# SCH.net
KiCad netlist of a schematic drawn in Altium Designer
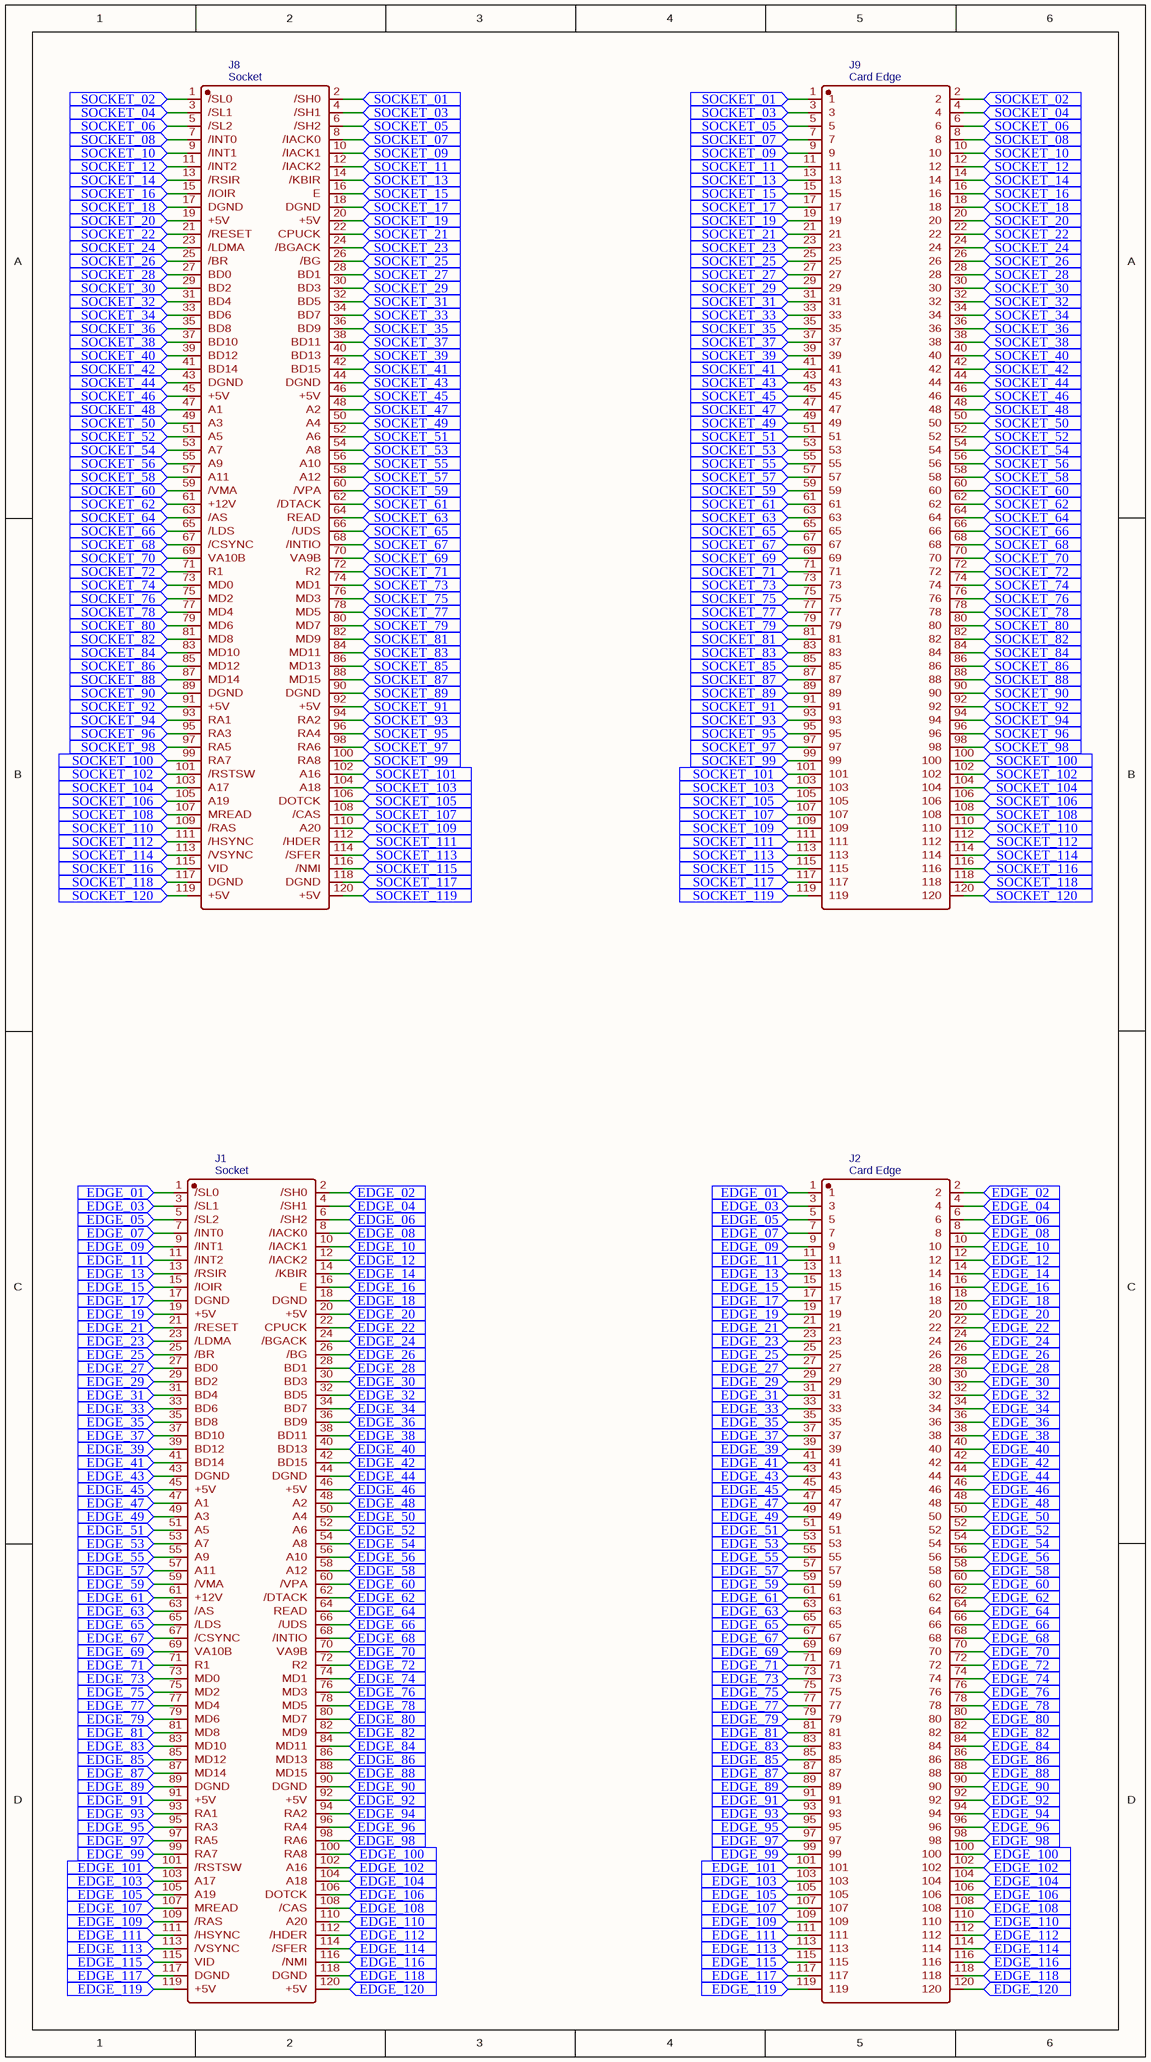
[diagram p0: SCH.schdoc]

(export (version "E")
  (design (tool "Eeschema 10.0.6"))
  (components
    (comp (ref "J1")
      (value "Socket")
      (fields
        (field (name "BOM_MANUFACTURER PART") "345-120-520-201")
        (field (name "BOM_SUPPLIER PART") "587-345-120-520-201")
        (field (name "CONTRIBUTOR") "AlexTheCat123")
      )
      (libsource (lib "altium-import") (part "root_0_Socket_"))
    )
    (comp (ref "J2")
      (value "Card Edge")
      (fields
        (field (name "BOM_MANUFACTURER PART") "345-120-520-201")
        (field (name "BOM_SUPPLIER PART") "587-345-120-520-201")
        (field (name "CONTRIBUTOR") "AlexTheCat123")
      )
      (libsource (lib "altium-import") (part "root_0_Card Edge_"))
    )
    (comp (ref "J8")
      (value "Socket")
      (fields
        (field (name "BOM_MANUFACTURER PART") "345-120-520-201")
        (field (name "BOM_SUPPLIER PART") "587-345-120-520-201")
        (field (name "CONTRIBUTOR") "AlexTheCat123")
      )
      (libsource (lib "altium-import") (part "root_0_Socket_"))
    )
    (comp (ref "J9")
      (value "Card Edge")
      (fields
        (field (name "BOM_MANUFACTURER PART") "345-120-520-201")
        (field (name "BOM_SUPPLIER PART") "587-345-120-520-201")
        (field (name "CONTRIBUTOR") "AlexTheCat123")
      )
      (libsource (lib "altium-import") (part "root_0_Card Edge_"))
    )
  )
  (nets
    (net (code "1") (name "/EDGE_01") (class "Default")
      (node (ref "J1") (pin "1") (pinfunction "/SL0_1") (pintype "passive"))
      (node (ref "J2") (pin "1") (pinfunction "1_1") (pintype "passive"))
    )
    (net (code "2") (name "/EDGE_02") (class "Default")
      (node (ref "J1") (pin "2") (pinfunction "/SH0_2") (pintype "passive"))
      (node (ref "J2") (pin "2") (pinfunction "2_2") (pintype "passive"))
    )
    (net (code "3") (name "/EDGE_03") (class "Default")
      (node (ref "J1") (pin "3") (pinfunction "/SL1_3") (pintype "passive"))
      (node (ref "J2") (pin "3") (pinfunction "3_3") (pintype "passive"))
    )
    (net (code "4") (name "/EDGE_04") (class "Default")
      (node (ref "J1") (pin "4") (pinfunction "/SH1_4") (pintype "passive"))
      (node (ref "J2") (pin "4") (pinfunction "4_4") (pintype "passive"))
    )
    (net (code "5") (name "/EDGE_05") (class "Default")
      (node (ref "J1") (pin "5") (pinfunction "/SL2_5") (pintype "passive"))
      (node (ref "J2") (pin "5") (pinfunction "5_5") (pintype "passive"))
    )
    (net (code "6") (name "/EDGE_06") (class "Default")
      (node (ref "J1") (pin "6") (pinfunction "/SH2_6") (pintype "passive"))
      (node (ref "J2") (pin "6") (pinfunction "6_6") (pintype "passive"))
    )
    (net (code "7") (name "/EDGE_07") (class "Default")
      (node (ref "J1") (pin "7") (pinfunction "/INT0_7") (pintype "passive"))
      (node (ref "J2") (pin "7") (pinfunction "7_7") (pintype "passive"))
    )
    (net (code "8") (name "/EDGE_08") (class "Default")
      (node (ref "J1") (pin "8") (pinfunction "/IACK0_8") (pintype "passive"))
      (node (ref "J2") (pin "8") (pinfunction "8_8") (pintype "passive"))
    )
    (net (code "9") (name "/EDGE_09") (class "Default")
      (node (ref "J1") (pin "9") (pinfunction "/INT1_9") (pintype "passive"))
      (node (ref "J2") (pin "9") (pinfunction "9_9") (pintype "passive"))
    )
    (net (code "10") (name "/EDGE_10") (class "Default")
      (node (ref "J1") (pin "10") (pinfunction "/IACK1_10") (pintype "passive"))
      (node (ref "J2") (pin "10") (pinfunction "10_10") (pintype "passive"))
    )
    (net (code "11") (name "/EDGE_11") (class "Default")
      (node (ref "J1") (pin "11") (pinfunction "/INT2_11") (pintype "passive"))
      (node (ref "J2") (pin "11") (pinfunction "11_11") (pintype "passive"))
    )
    (net (code "12") (name "/EDGE_12") (class "Default")
      (node (ref "J1") (pin "12") (pinfunction "/IACK2_12") (pintype "passive"))
      (node (ref "J2") (pin "12") (pinfunction "12_12") (pintype "passive"))
    )
    (net (code "13") (name "/EDGE_13") (class "Default")
      (node (ref "J1") (pin "13") (pinfunction "/RSIR_13") (pintype "passive"))
      (node (ref "J2") (pin "13") (pinfunction "13_13") (pintype "passive"))
    )
    (net (code "14") (name "/EDGE_14") (class "Default")
      (node (ref "J1") (pin "14") (pinfunction "/KBIR_14") (pintype "passive"))
      (node (ref "J2") (pin "14") (pinfunction "14_14") (pintype "passive"))
    )
    (net (code "15") (name "/EDGE_15") (class "Default")
      (node (ref "J1") (pin "15") (pinfunction "/IOIR_15") (pintype "passive"))
      (node (ref "J2") (pin "15") (pinfunction "15_15") (pintype "passive"))
    )
    (net (code "16") (name "/EDGE_16") (class "Default")
      (node (ref "J1") (pin "16") (pinfunction "E_16") (pintype "passive"))
      (node (ref "J2") (pin "16") (pinfunction "16_16") (pintype "passive"))
    )
    (net (code "17") (name "/EDGE_17") (class "Default")
      (node (ref "J1") (pin "17") (pinfunction "DGND_17") (pintype "passive"))
      (node (ref "J2") (pin "17") (pinfunction "17_17") (pintype "passive"))
    )
    (net (code "18") (name "/EDGE_18") (class "Default")
      (node (ref "J1") (pin "18") (pinfunction "DGND_18") (pintype "passive"))
      (node (ref "J2") (pin "18") (pinfunction "18_18") (pintype "passive"))
    )
    (net (code "19") (name "/EDGE_19") (class "Default")
      (node (ref "J1") (pin "19") (pinfunction "+5V_19") (pintype "passive"))
      (node (ref "J2") (pin "19") (pinfunction "19_19") (pintype "passive"))
    )
    (net (code "20") (name "/EDGE_20") (class "Default")
      (node (ref "J1") (pin "20") (pinfunction "+5V_20") (pintype "passive"))
      (node (ref "J2") (pin "20") (pinfunction "20_20") (pintype "passive"))
    )
    (net (code "21") (name "/EDGE_21") (class "Default")
      (node (ref "J1") (pin "21") (pinfunction "/RESET_21") (pintype "passive"))
      (node (ref "J2") (pin "21") (pinfunction "21_21") (pintype "passive"))
    )
    (net (code "22") (name "/EDGE_22") (class "Default")
      (node (ref "J1") (pin "22") (pinfunction "CPUCK_22") (pintype "passive"))
      (node (ref "J2") (pin "22") (pinfunction "22_22") (pintype "passive"))
    )
    (net (code "23") (name "/EDGE_23") (class "Default")
      (node (ref "J1") (pin "23") (pinfunction "/LDMA_23") (pintype "passive"))
      (node (ref "J2") (pin "23") (pinfunction "23_23") (pintype "passive"))
    )
    (net (code "24") (name "/EDGE_24") (class "Default")
      (node (ref "J1") (pin "24") (pinfunction "/BGACK_24") (pintype "passive"))
      (node (ref "J2") (pin "24") (pinfunction "24_24") (pintype "passive"))
    )
    (net (code "25") (name "/EDGE_25") (class "Default")
      (node (ref "J1") (pin "25") (pinfunction "/BR_25") (pintype "passive"))
      (node (ref "J2") (pin "25") (pinfunction "25_25") (pintype "passive"))
    )
    (net (code "26") (name "/EDGE_26") (class "Default")
      (node (ref "J1") (pin "26") (pinfunction "/BG_26") (pintype "passive"))
      (node (ref "J2") (pin "26") (pinfunction "26_26") (pintype "passive"))
    )
    (net (code "27") (name "/EDGE_27") (class "Default")
      (node (ref "J1") (pin "27") (pinfunction "BD0_27") (pintype "passive"))
      (node (ref "J2") (pin "27") (pinfunction "27_27") (pintype "passive"))
    )
    (net (code "28") (name "/EDGE_28") (class "Default")
      (node (ref "J1") (pin "28") (pinfunction "BD1_28") (pintype "passive"))
      (node (ref "J2") (pin "28") (pinfunction "28_28") (pintype "passive"))
    )
    (net (code "29") (name "/EDGE_29") (class "Default")
      (node (ref "J1") (pin "29") (pinfunction "BD2_29") (pintype "passive"))
      (node (ref "J2") (pin "29") (pinfunction "29_29") (pintype "passive"))
    )
    (net (code "30") (name "/EDGE_30") (class "Default")
      (node (ref "J1") (pin "30") (pinfunction "BD3_30") (pintype "passive"))
      (node (ref "J2") (pin "30") (pinfunction "30_30") (pintype "passive"))
    )
    (net (code "31") (name "/EDGE_31") (class "Default")
      (node (ref "J1") (pin "31") (pinfunction "BD4_31") (pintype "passive"))
      (node (ref "J2") (pin "31") (pinfunction "31_31") (pintype "passive"))
    )
    (net (code "32") (name "/EDGE_32") (class "Default")
      (node (ref "J1") (pin "32") (pinfunction "BD5_32") (pintype "passive"))
      (node (ref "J2") (pin "32") (pinfunction "32_32") (pintype "passive"))
    )
    (net (code "33") (name "/EDGE_33") (class "Default")
      (node (ref "J1") (pin "33") (pinfunction "BD6_33") (pintype "passive"))
      (node (ref "J2") (pin "33") (pinfunction "33_33") (pintype "passive"))
    )
    (net (code "34") (name "/EDGE_34") (class "Default")
      (node (ref "J1") (pin "34") (pinfunction "BD7_34") (pintype "passive"))
      (node (ref "J2") (pin "34") (pinfunction "34_34") (pintype "passive"))
    )
    (net (code "35") (name "/EDGE_35") (class "Default")
      (node (ref "J1") (pin "35") (pinfunction "BD8_35") (pintype "passive"))
      (node (ref "J2") (pin "35") (pinfunction "35_35") (pintype "passive"))
    )
    (net (code "36") (name "/EDGE_36") (class "Default")
      (node (ref "J1") (pin "36") (pinfunction "BD9_36") (pintype "passive"))
      (node (ref "J2") (pin "36") (pinfunction "36_36") (pintype "passive"))
    )
    (net (code "37") (name "/EDGE_37") (class "Default")
      (node (ref "J1") (pin "37") (pinfunction "BD10_37") (pintype "passive"))
      (node (ref "J2") (pin "37") (pinfunction "37_37") (pintype "passive"))
    )
    (net (code "38") (name "/EDGE_38") (class "Default")
      (node (ref "J1") (pin "38") (pinfunction "BD11_38") (pintype "passive"))
      (node (ref "J2") (pin "38") (pinfunction "38_38") (pintype "passive"))
    )
    (net (code "39") (name "/EDGE_39") (class "Default")
      (node (ref "J1") (pin "39") (pinfunction "BD12_39") (pintype "passive"))
      (node (ref "J2") (pin "39") (pinfunction "39_39") (pintype "passive"))
    )
    (net (code "40") (name "/EDGE_40") (class "Default")
      (node (ref "J1") (pin "40") (pinfunction "BD13_40") (pintype "passive"))
      (node (ref "J2") (pin "40") (pinfunction "40_40") (pintype "passive"))
    )
    (net (code "41") (name "/EDGE_41") (class "Default")
      (node (ref "J1") (pin "41") (pinfunction "BD14_41") (pintype "passive"))
      (node (ref "J2") (pin "41") (pinfunction "41_41") (pintype "passive"))
    )
    (net (code "42") (name "/EDGE_42") (class "Default")
      (node (ref "J1") (pin "42") (pinfunction "BD15_42") (pintype "passive"))
      (node (ref "J2") (pin "42") (pinfunction "42_42") (pintype "passive"))
    )
    (net (code "43") (name "/EDGE_43") (class "Default")
      (node (ref "J1") (pin "43") (pinfunction "DGND_43") (pintype "passive"))
      (node (ref "J2") (pin "43") (pinfunction "43_43") (pintype "passive"))
    )
    (net (code "44") (name "/EDGE_44") (class "Default")
      (node (ref "J1") (pin "44") (pinfunction "DGND_44") (pintype "passive"))
      (node (ref "J2") (pin "44") (pinfunction "44_44") (pintype "passive"))
    )
    (net (code "45") (name "/EDGE_45") (class "Default")
      (node (ref "J1") (pin "45") (pinfunction "+5V_45") (pintype "passive"))
      (node (ref "J2") (pin "45") (pinfunction "45_45") (pintype "passive"))
    )
    (net (code "46") (name "/EDGE_46") (class "Default")
      (node (ref "J1") (pin "46") (pinfunction "+5V_46") (pintype "passive"))
      (node (ref "J2") (pin "46") (pinfunction "46_46") (pintype "passive"))
    )
    (net (code "47") (name "/EDGE_47") (class "Default")
      (node (ref "J1") (pin "47") (pinfunction "A1_47") (pintype "passive"))
      (node (ref "J2") (pin "47") (pinfunction "47_47") (pintype "passive"))
    )
    (net (code "48") (name "/EDGE_48") (class "Default")
      (node (ref "J1") (pin "48") (pinfunction "A2_48") (pintype "passive"))
      (node (ref "J2") (pin "48") (pinfunction "48_48") (pintype "passive"))
    )
    (net (code "49") (name "/EDGE_49") (class "Default")
      (node (ref "J1") (pin "49") (pinfunction "A3_49") (pintype "passive"))
      (node (ref "J2") (pin "49") (pinfunction "49_49") (pintype "passive"))
    )
    (net (code "50") (name "/EDGE_50") (class "Default")
      (node (ref "J1") (pin "50") (pinfunction "A4_50") (pintype "passive"))
      (node (ref "J2") (pin "50") (pinfunction "50_50") (pintype "passive"))
    )
    (net (code "51") (name "/EDGE_51") (class "Default")
      (node (ref "J1") (pin "51") (pinfunction "A5_51") (pintype "passive"))
      (node (ref "J2") (pin "51") (pinfunction "51_51") (pintype "passive"))
    )
    (net (code "52") (name "/EDGE_52") (class "Default")
      (node (ref "J1") (pin "52") (pinfunction "A6_52") (pintype "passive"))
      (node (ref "J2") (pin "52") (pinfunction "52_52") (pintype "passive"))
    )
    (net (code "53") (name "/EDGE_53") (class "Default")
      (node (ref "J1") (pin "53") (pinfunction "A7_53") (pintype "passive"))
      (node (ref "J2") (pin "53") (pinfunction "53_53") (pintype "passive"))
    )
    (net (code "54") (name "/EDGE_54") (class "Default")
      (node (ref "J1") (pin "54") (pinfunction "A8_54") (pintype "passive"))
      (node (ref "J2") (pin "54") (pinfunction "54_54") (pintype "passive"))
    )
    (net (code "55") (name "/EDGE_55") (class "Default")
      (node (ref "J1") (pin "55") (pinfunction "A9_55") (pintype "passive"))
      (node (ref "J2") (pin "55") (pinfunction "55_55") (pintype "passive"))
    )
    (net (code "56") (name "/EDGE_56") (class "Default")
      (node (ref "J1") (pin "56") (pinfunction "A10_56") (pintype "passive"))
      (node (ref "J2") (pin "56") (pinfunction "56_56") (pintype "passive"))
    )
    (net (code "57") (name "/EDGE_57") (class "Default")
      (node (ref "J1") (pin "57") (pinfunction "A11_57") (pintype "passive"))
      (node (ref "J2") (pin "57") (pinfunction "57_57") (pintype "passive"))
    )
    (net (code "58") (name "/EDGE_58") (class "Default")
      (node (ref "J1") (pin "58") (pinfunction "A12_58") (pintype "passive"))
      (node (ref "J2") (pin "58") (pinfunction "58_58") (pintype "passive"))
    )
    (net (code "59") (name "/EDGE_59") (class "Default")
      (node (ref "J1") (pin "59") (pinfunction "/VMA_59") (pintype "passive"))
      (node (ref "J2") (pin "59") (pinfunction "59_59") (pintype "passive"))
    )
    (net (code "60") (name "/EDGE_60") (class "Default")
      (node (ref "J1") (pin "60") (pinfunction "/VPA_60") (pintype "passive"))
      (node (ref "J2") (pin "60") (pinfunction "60_60") (pintype "passive"))
    )
    (net (code "61") (name "/EDGE_61") (class "Default")
      (node (ref "J1") (pin "61") (pinfunction "+12V_61") (pintype "passive"))
      (node (ref "J2") (pin "61") (pinfunction "61_61") (pintype "passive"))
    )
    (net (code "62") (name "/EDGE_62") (class "Default")
      (node (ref "J1") (pin "62") (pinfunction "/DTACK_62") (pintype "passive"))
      (node (ref "J2") (pin "62") (pinfunction "62_62") (pintype "passive"))
    )
    (net (code "63") (name "/EDGE_63") (class "Default")
      (node (ref "J1") (pin "63") (pinfunction "/AS_63") (pintype "passive"))
      (node (ref "J2") (pin "63") (pinfunction "63_63") (pintype "passive"))
    )
    (net (code "64") (name "/EDGE_64") (class "Default")
      (node (ref "J1") (pin "64") (pinfunction "READ_64") (pintype "passive"))
      (node (ref "J2") (pin "64") (pinfunction "64_64") (pintype "passive"))
    )
    (net (code "65") (name "/EDGE_65") (class "Default")
      (node (ref "J1") (pin "65") (pinfunction "/LDS_65") (pintype "passive"))
      (node (ref "J2") (pin "65") (pinfunction "65_65") (pintype "passive"))
    )
    (net (code "66") (name "/EDGE_66") (class "Default")
      (node (ref "J1") (pin "66") (pinfunction "/UDS_66") (pintype "passive"))
      (node (ref "J2") (pin "66") (pinfunction "66_66") (pintype "passive"))
    )
    (net (code "67") (name "/EDGE_67") (class "Default")
      (node (ref "J1") (pin "67") (pinfunction "/CSYNC_67") (pintype "passive"))
      (node (ref "J2") (pin "67") (pinfunction "67_67") (pintype "passive"))
    )
    (net (code "68") (name "/EDGE_68") (class "Default")
      (node (ref "J1") (pin "68") (pinfunction "/INTIO_68") (pintype "passive"))
      (node (ref "J2") (pin "68") (pinfunction "68_68") (pintype "passive"))
    )
    (net (code "69") (name "/EDGE_69") (class "Default")
      (node (ref "J1") (pin "69") (pinfunction "VA10B_69") (pintype "passive"))
      (node (ref "J2") (pin "69") (pinfunction "69_69") (pintype "passive"))
    )
    (net (code "70") (name "/EDGE_70") (class "Default")
      (node (ref "J1") (pin "70") (pinfunction "VA9B_70") (pintype "passive"))
      (node (ref "J2") (pin "70") (pinfunction "70_70") (pintype "passive"))
    )
    (net (code "71") (name "/EDGE_71") (class "Default")
      (node (ref "J1") (pin "71") (pinfunction "R1_71") (pintype "passive"))
      (node (ref "J2") (pin "71") (pinfunction "71_71") (pintype "passive"))
    )
    (net (code "72") (name "/EDGE_72") (class "Default")
      (node (ref "J1") (pin "72") (pinfunction "R2_72") (pintype "passive"))
      (node (ref "J2") (pin "72") (pinfunction "72_72") (pintype "passive"))
    )
    (net (code "73") (name "/EDGE_73") (class "Default")
      (node (ref "J1") (pin "73") (pinfunction "MD0_73") (pintype "passive"))
      (node (ref "J2") (pin "73") (pinfunction "73_73") (pintype "passive"))
    )
    (net (code "74") (name "/EDGE_74") (class "Default")
      (node (ref "J1") (pin "74") (pinfunction "MD1_74") (pintype "passive"))
      (node (ref "J2") (pin "74") (pinfunction "74_74") (pintype "passive"))
    )
    (net (code "75") (name "/EDGE_75") (class "Default")
      (node (ref "J1") (pin "75") (pinfunction "MD2_75") (pintype "passive"))
      (node (ref "J2") (pin "75") (pinfunction "75_75") (pintype "passive"))
    )
    (net (code "76") (name "/EDGE_76") (class "Default")
      (node (ref "J1") (pin "76") (pinfunction "MD3_76") (pintype "passive"))
      (node (ref "J2") (pin "76") (pinfunction "76_76") (pintype "passive"))
    )
    (net (code "77") (name "/EDGE_77") (class "Default")
      (node (ref "J1") (pin "77") (pinfunction "MD4_77") (pintype "passive"))
      (node (ref "J2") (pin "77") (pinfunction "77_77") (pintype "passive"))
    )
    (net (code "78") (name "/EDGE_78") (class "Default")
      (node (ref "J1") (pin "78") (pinfunction "MD5_78") (pintype "passive"))
      (node (ref "J2") (pin "78") (pinfunction "78_78") (pintype "passive"))
    )
    (net (code "79") (name "/EDGE_79") (class "Default")
      (node (ref "J1") (pin "79") (pinfunction "MD6_79") (pintype "passive"))
      (node (ref "J2") (pin "79") (pinfunction "79_79") (pintype "passive"))
    )
    (net (code "80") (name "/EDGE_80") (class "Default")
      (node (ref "J1") (pin "80") (pinfunction "MD7_80") (pintype "passive"))
      (node (ref "J2") (pin "80") (pinfunction "80_80") (pintype "passive"))
    )
    (net (code "81") (name "/EDGE_81") (class "Default")
      (node (ref "J1") (pin "81") (pinfunction "MD8_81") (pintype "passive"))
      (node (ref "J2") (pin "81") (pinfunction "81_81") (pintype "passive"))
    )
    (net (code "82") (name "/EDGE_82") (class "Default")
      (node (ref "J1") (pin "82") (pinfunction "MD9_82") (pintype "passive"))
      (node (ref "J2") (pin "82") (pinfunction "82_82") (pintype "passive"))
    )
    (net (code "83") (name "/EDGE_83") (class "Default")
      (node (ref "J1") (pin "83") (pinfunction "MD10_83") (pintype "passive"))
      (node (ref "J2") (pin "83") (pinfunction "83_83") (pintype "passive"))
    )
    (net (code "84") (name "/EDGE_84") (class "Default")
      (node (ref "J1") (pin "84") (pinfunction "MD11_84") (pintype "passive"))
      (node (ref "J2") (pin "84") (pinfunction "84_84") (pintype "passive"))
    )
    (net (code "85") (name "/EDGE_85") (class "Default")
      (node (ref "J1") (pin "85") (pinfunction "MD12_85") (pintype "passive"))
      (node (ref "J2") (pin "85") (pinfunction "85_85") (pintype "passive"))
    )
    (net (code "86") (name "/EDGE_86") (class "Default")
      (node (ref "J1") (pin "86") (pinfunction "MD13_86") (pintype "passive"))
      (node (ref "J2") (pin "86") (pinfunction "86_86") (pintype "passive"))
    )
    (net (code "87") (name "/EDGE_87") (class "Default")
      (node (ref "J1") (pin "87") (pinfunction "MD14_87") (pintype "passive"))
      (node (ref "J2") (pin "87") (pinfunction "87_87") (pintype "passive"))
    )
    (net (code "88") (name "/EDGE_88") (class "Default")
      (node (ref "J1") (pin "88") (pinfunction "MD15_88") (pintype "passive"))
      (node (ref "J2") (pin "88") (pinfunction "88_88") (pintype "passive"))
    )
    (net (code "89") (name "/EDGE_89") (class "Default")
      (node (ref "J1") (pin "89") (pinfunction "DGND_89") (pintype "passive"))
      (node (ref "J2") (pin "89") (pinfunction "89_89") (pintype "passive"))
    )
    (net (code "90") (name "/EDGE_90") (class "Default")
      (node (ref "J1") (pin "90") (pinfunction "DGND_90") (pintype "passive"))
      (node (ref "J2") (pin "90") (pinfunction "90_90") (pintype "passive"))
    )
    (net (code "91") (name "/EDGE_91") (class "Default")
      (node (ref "J1") (pin "91") (pinfunction "+5V_91") (pintype "passive"))
      (node (ref "J2") (pin "91") (pinfunction "91_91") (pintype "passive"))
    )
    (net (code "92") (name "/EDGE_92") (class "Default")
      (node (ref "J1") (pin "92") (pinfunction "+5V_92") (pintype "passive"))
      (node (ref "J2") (pin "92") (pinfunction "92_92") (pintype "passive"))
    )
    (net (code "93") (name "/EDGE_93") (class "Default")
      (node (ref "J1") (pin "93") (pinfunction "RA1_93") (pintype "passive"))
      (node (ref "J2") (pin "93") (pinfunction "93_93") (pintype "passive"))
    )
    (net (code "94") (name "/EDGE_94") (class "Default")
      (node (ref "J1") (pin "94") (pinfunction "RA2_94") (pintype "passive"))
      (node (ref "J2") (pin "94") (pinfunction "94_94") (pintype "passive"))
    )
    (net (code "95") (name "/EDGE_95") (class "Default")
      (node (ref "J1") (pin "95") (pinfunction "RA3_95") (pintype "passive"))
      (node (ref "J2") (pin "95") (pinfunction "95_95") (pintype "passive"))
    )
    (net (code "96") (name "/EDGE_96") (class "Default")
      (node (ref "J1") (pin "96") (pinfunction "RA4_96") (pintype "passive"))
      (node (ref "J2") (pin "96") (pinfunction "96_96") (pintype "passive"))
    )
    (net (code "97") (name "/EDGE_97") (class "Default")
      (node (ref "J1") (pin "97") (pinfunction "RA5_97") (pintype "passive"))
      (node (ref "J2") (pin "97") (pinfunction "97_97") (pintype "passive"))
    )
    (net (code "98") (name "/EDGE_98") (class "Default")
      (node (ref "J1") (pin "98") (pinfunction "RA6_98") (pintype "passive"))
      (node (ref "J2") (pin "98") (pinfunction "98_98") (pintype "passive"))
    )
    (net (code "99") (name "/EDGE_99") (class "Default")
      (node (ref "J1") (pin "99") (pinfunction "RA7_99") (pintype "passive"))
      (node (ref "J2") (pin "99") (pinfunction "99_99") (pintype "passive"))
    )
    (net (code "100") (name "/EDGE_100") (class "Default")
      (node (ref "J1") (pin "100") (pinfunction "RA8_100") (pintype "passive"))
      (node (ref "J2") (pin "100") (pinfunction "100_100") (pintype "passive"))
    )
    (net (code "101") (name "/EDGE_101") (class "Default")
      (node (ref "J1") (pin "101") (pinfunction "/RSTSW_101") (pintype "passive"))
      (node (ref "J2") (pin "101") (pinfunction "101_101") (pintype "passive"))
    )
    (net (code "102") (name "/EDGE_102") (class "Default")
      (node (ref "J1") (pin "102") (pinfunction "A16_102") (pintype "passive"))
      (node (ref "J2") (pin "102") (pinfunction "102_102") (pintype "passive"))
    )
    (net (code "103") (name "/EDGE_103") (class "Default")
      (node (ref "J1") (pin "103") (pinfunction "A17_103") (pintype "passive"))
      (node (ref "J2") (pin "103") (pinfunction "103_103") (pintype "passive"))
    )
    (net (code "104") (name "/EDGE_104") (class "Default")
      (node (ref "J1") (pin "104") (pinfunction "A18_104") (pintype "passive"))
      (node (ref "J2") (pin "104") (pinfunction "104_104") (pintype "passive"))
    )
    (net (code "105") (name "/EDGE_105") (class "Default")
      (node (ref "J1") (pin "105") (pinfunction "A19_105") (pintype "passive"))
      (node (ref "J2") (pin "105") (pinfunction "105_105") (pintype "passive"))
    )
    (net (code "106") (name "/EDGE_106") (class "Default")
      (node (ref "J1") (pin "106") (pinfunction "DOTCK_106") (pintype "passive"))
      (node (ref "J2") (pin "106") (pinfunction "106_106") (pintype "passive"))
    )
    (net (code "107") (name "/EDGE_107") (class "Default")
      (node (ref "J1") (pin "107") (pinfunction "MREAD_107") (pintype "passive"))
      (node (ref "J2") (pin "107") (pinfunction "107_107") (pintype "passive"))
    )
    (net (code "108") (name "/EDGE_108") (class "Default")
      (node (ref "J1") (pin "108") (pinfunction "/CAS_108") (pintype "passive"))
      (node (ref "J2") (pin "108") (pinfunction "108_108") (pintype "passive"))
    )
    (net (code "109") (name "/EDGE_109") (class "Default")
      (node (ref "J1") (pin "109") (pinfunction "/RAS_109") (pintype "passive"))
      (node (ref "J2") (pin "109") (pinfunction "109_109") (pintype "passive"))
    )
    (net (code "110") (name "/EDGE_110") (class "Default")
      (node (ref "J1") (pin "110") (pinfunction "A20_110") (pintype "passive"))
      (node (ref "J2") (pin "110") (pinfunction "110_110") (pintype "passive"))
    )
    (net (code "111") (name "/EDGE_111") (class "Default")
      (node (ref "J1") (pin "111") (pinfunction "/HSYNC_111") (pintype "passive"))
      (node (ref "J2") (pin "111") (pinfunction "111_111") (pintype "passive"))
    )
    (net (code "112") (name "/EDGE_112") (class "Default")
      (node (ref "J1") (pin "112") (pinfunction "/HDER_112") (pintype "passive"))
      (node (ref "J2") (pin "112") (pinfunction "112_112") (pintype "passive"))
    )
    (net (code "113") (name "/EDGE_113") (class "Default")
      (node (ref "J1") (pin "113") (pinfunction "/VSYNC_113") (pintype "passive"))
      (node (ref "J2") (pin "113") (pinfunction "113_113") (pintype "passive"))
    )
    (net (code "114") (name "/EDGE_114") (class "Default")
      (node (ref "J1") (pin "114") (pinfunction "/SFER_114") (pintype "passive"))
      (node (ref "J2") (pin "114") (pinfunction "114_114") (pintype "passive"))
    )
    (net (code "115") (name "/EDGE_115") (class "Default")
      (node (ref "J1") (pin "115") (pinfunction "VID_115") (pintype "passive"))
      (node (ref "J2") (pin "115") (pinfunction "115_115") (pintype "passive"))
    )
    (net (code "116") (name "/EDGE_116") (class "Default")
      (node (ref "J1") (pin "116") (pinfunction "/NMI_116") (pintype "passive"))
      (node (ref "J2") (pin "116") (pinfunction "116_116") (pintype "passive"))
    )
    (net (code "117") (name "/EDGE_117") (class "Default")
      (node (ref "J1") (pin "117") (pinfunction "DGND_117") (pintype "passive"))
      (node (ref "J2") (pin "117") (pinfunction "117_117") (pintype "passive"))
    )
    (net (code "118") (name "/EDGE_118") (class "Default")
      (node (ref "J1") (pin "118") (pinfunction "DGND_118") (pintype "passive"))
      (node (ref "J2") (pin "118") (pinfunction "118_118") (pintype "passive"))
    )
    (net (code "119") (name "/EDGE_119") (class "Default")
      (node (ref "J1") (pin "119") (pinfunction "+5V_119") (pintype "passive"))
      (node (ref "J2") (pin "119") (pinfunction "119_119") (pintype "passive"))
    )
    (net (code "120") (name "/EDGE_120") (class "Default")
      (node (ref "J1") (pin "120") (pinfunction "+5V_120") (pintype "passive"))
      (node (ref "J2") (pin "120") (pinfunction "120_120") (pintype "passive"))
    )
    (net (code "121") (name "/SOCKET_01") (class "Default")
      (node (ref "J8") (pin "2") (pinfunction "/SH0_2") (pintype "passive"))
      (node (ref "J9") (pin "1") (pinfunction "1_1") (pintype "passive"))
    )
    (net (code "122") (name "/SOCKET_02") (class "Default")
      (node (ref "J8") (pin "1") (pinfunction "/SL0_1") (pintype "passive"))
      (node (ref "J9") (pin "2") (pinfunction "2_2") (pintype "passive"))
    )
    (net (code "123") (name "/SOCKET_03") (class "Default")
      (node (ref "J8") (pin "4") (pinfunction "/SH1_4") (pintype "passive"))
      (node (ref "J9") (pin "3") (pinfunction "3_3") (pintype "passive"))
    )
    (net (code "124") (name "/SOCKET_04") (class "Default")
      (node (ref "J8") (pin "3") (pinfunction "/SL1_3") (pintype "passive"))
      (node (ref "J9") (pin "4") (pinfunction "4_4") (pintype "passive"))
    )
    (net (code "125") (name "/SOCKET_05") (class "Default")
      (node (ref "J8") (pin "6") (pinfunction "/SH2_6") (pintype "passive"))
      (node (ref "J9") (pin "5") (pinfunction "5_5") (pintype "passive"))
    )
    (net (code "126") (name "/SOCKET_06") (class "Default")
      (node (ref "J8") (pin "5") (pinfunction "/SL2_5") (pintype "passive"))
      (node (ref "J9") (pin "6") (pinfunction "6_6") (pintype "passive"))
    )
    (net (code "127") (name "/SOCKET_07") (class "Default")
      (node (ref "J8") (pin "8") (pinfunction "/IACK0_8") (pintype "passive"))
      (node (ref "J9") (pin "7") (pinfunction "7_7") (pintype "passive"))
    )
    (net (code "128") (name "/SOCKET_08") (class "Default")
      (node (ref "J8") (pin "7") (pinfunction "/INT0_7") (pintype "passive"))
      (node (ref "J9") (pin "8") (pinfunction "8_8") (pintype "passive"))
    )
    (net (code "129") (name "/SOCKET_09") (class "Default")
      (node (ref "J8") (pin "10") (pinfunction "/IACK1_10") (pintype "passive"))
      (node (ref "J9") (pin "9") (pinfunction "9_9") (pintype "passive"))
    )
    (net (code "130") (name "/SOCKET_10") (class "Default")
      (node (ref "J8") (pin "9") (pinfunction "/INT1_9") (pintype "passive"))
      (node (ref "J9") (pin "10") (pinfunction "10_10") (pintype "passive"))
    )
    (net (code "131") (name "/SOCKET_11") (class "Default")
      (node (ref "J8") (pin "12") (pinfunction "/IACK2_12") (pintype "passive"))
      (node (ref "J9") (pin "11") (pinfunction "11_11") (pintype "passive"))
    )
    (net (code "132") (name "/SOCKET_12") (class "Default")
      (node (ref "J8") (pin "11") (pinfunction "/INT2_11") (pintype "passive"))
      (node (ref "J9") (pin "12") (pinfunction "12_12") (pintype "passive"))
    )
    (net (code "133") (name "/SOCKET_13") (class "Default")
      (node (ref "J8") (pin "14") (pinfunction "/KBIR_14") (pintype "passive"))
      (node (ref "J9") (pin "13") (pinfunction "13_13") (pintype "passive"))
    )
    (net (code "134") (name "/SOCKET_14") (class "Default")
      (node (ref "J8") (pin "13") (pinfunction "/RSIR_13") (pintype "passive"))
      (node (ref "J9") (pin "14") (pinfunction "14_14") (pintype "passive"))
    )
    (net (code "135") (name "/SOCKET_15") (class "Default")
      (node (ref "J8") (pin "16") (pinfunction "E_16") (pintype "passive"))
      (node (ref "J9") (pin "15") (pinfunction "15_15") (pintype "passive"))
    )
    (net (code "136") (name "/SOCKET_16") (class "Default")
      (node (ref "J8") (pin "15") (pinfunction "/IOIR_15") (pintype "passive"))
      (node (ref "J9") (pin "16") (pinfunction "16_16") (pintype "passive"))
    )
    (net (code "137") (name "/SOCKET_17") (class "Default")
      (node (ref "J8") (pin "18") (pinfunction "DGND_18") (pintype "passive"))
      (node (ref "J9") (pin "17") (pinfunction "17_17") (pintype "passive"))
    )
    (net (code "138") (name "/SOCKET_18") (class "Default")
      (node (ref "J8") (pin "17") (pinfunction "DGND_17") (pintype "passive"))
      (node (ref "J9") (pin "18") (pinfunction "18_18") (pintype "passive"))
    )
    (net (code "139") (name "/SOCKET_19") (class "Default")
      (node (ref "J8") (pin "20") (pinfunction "+5V_20") (pintype "passive"))
      (node (ref "J9") (pin "19") (pinfunction "19_19") (pintype "passive"))
    )
    (net (code "140") (name "/SOCKET_20") (class "Default")
      (node (ref "J8") (pin "19") (pinfunction "+5V_19") (pintype "passive"))
      (node (ref "J9") (pin "20") (pinfunction "20_20") (pintype "passive"))
    )
    (net (code "141") (name "/SOCKET_21") (class "Default")
      (node (ref "J8") (pin "22") (pinfunction "CPUCK_22") (pintype "passive"))
      (node (ref "J9") (pin "21") (pinfunction "21_21") (pintype "passive"))
    )
    (net (code "142") (name "/SOCKET_22") (class "Default")
      (node (ref "J8") (pin "21") (pinfunction "/RESET_21") (pintype "passive"))
      (node (ref "J9") (pin "22") (pinfunction "22_22") (pintype "passive"))
    )
    (net (code "143") (name "/SOCKET_23") (class "Default")
      (node (ref "J8") (pin "24") (pinfunction "/BGACK_24") (pintype "passive"))
      (node (ref "J9") (pin "23") (pinfunction "23_23") (pintype "passive"))
    )
    (net (code "144") (name "/SOCKET_24") (class "Default")
      (node (ref "J8") (pin "23") (pinfunction "/LDMA_23") (pintype "passive"))
      (node (ref "J9") (pin "24") (pinfunction "24_24") (pintype "passive"))
    )
    (net (code "145") (name "/SOCKET_25") (class "Default")
      (node (ref "J8") (pin "26") (pinfunction "/BG_26") (pintype "passive"))
      (node (ref "J9") (pin "25") (pinfunction "25_25") (pintype "passive"))
    )
    (net (code "146") (name "/SOCKET_26") (class "Default")
      (node (ref "J8") (pin "25") (pinfunction "/BR_25") (pintype "passive"))
      (node (ref "J9") (pin "26") (pinfunction "26_26") (pintype "passive"))
    )
    (net (code "147") (name "/SOCKET_27") (class "Default")
      (node (ref "J8") (pin "28") (pinfunction "BD1_28") (pintype "passive"))
      (node (ref "J9") (pin "27") (pinfunction "27_27") (pintype "passive"))
    )
    (net (code "148") (name "/SOCKET_28") (class "Default")
      (node (ref "J8") (pin "27") (pinfunction "BD0_27") (pintype "passive"))
      (node (ref "J9") (pin "28") (pinfunction "28_28") (pintype "passive"))
    )
    (net (code "149") (name "/SOCKET_29") (class "Default")
      (node (ref "J8") (pin "30") (pinfunction "BD3_30") (pintype "passive"))
      (node (ref "J9") (pin "29") (pinfunction "29_29") (pintype "passive"))
    )
    (net (code "150") (name "/SOCKET_30") (class "Default")
      (node (ref "J8") (pin "29") (pinfunction "BD2_29") (pintype "passive"))
      (node (ref "J9") (pin "30") (pinfunction "30_30") (pintype "passive"))
    )
    (net (code "151") (name "/SOCKET_31") (class "Default")
      (node (ref "J8") (pin "32") (pinfunction "BD5_32") (pintype "passive"))
      (node (ref "J9") (pin "31") (pinfunction "31_31") (pintype "passive"))
    )
    (net (code "152") (name "/SOCKET_32") (class "Default")
      (node (ref "J8") (pin "31") (pinfunction "BD4_31") (pintype "passive"))
      (node (ref "J9") (pin "32") (pinfunction "32_32") (pintype "passive"))
    )
    (net (code "153") (name "/SOCKET_33") (class "Default")
      (node (ref "J8") (pin "34") (pinfunction "BD7_34") (pintype "passive"))
      (node (ref "J9") (pin "33") (pinfunction "33_33") (pintype "passive"))
    )
    (net (code "154") (name "/SOCKET_34") (class "Default")
      (node (ref "J8") (pin "33") (pinfunction "BD6_33") (pintype "passive"))
      (node (ref "J9") (pin "34") (pinfunction "34_34") (pintype "passive"))
    )
    (net (code "155") (name "/SOCKET_35") (class "Default")
      (node (ref "J8") (pin "36") (pinfunction "BD9_36") (pintype "passive"))
      (node (ref "J9") (pin "35") (pinfunction "35_35") (pintype "passive"))
    )
    (net (code "156") (name "/SOCKET_36") (class "Default")
      (node (ref "J8") (pin "35") (pinfunction "BD8_35") (pintype "passive"))
      (node (ref "J9") (pin "36") (pinfunction "36_36") (pintype "passive"))
    )
    (net (code "157") (name "/SOCKET_37") (class "Default")
      (node (ref "J8") (pin "38") (pinfunction "BD11_38") (pintype "passive"))
      (node (ref "J9") (pin "37") (pinfunction "37_37") (pintype "passive"))
    )
    (net (code "158") (name "/SOCKET_38") (class "Default")
      (node (ref "J8") (pin "37") (pinfunction "BD10_37") (pintype "passive"))
      (node (ref "J9") (pin "38") (pinfunction "38_38") (pintype "passive"))
    )
    (net (code "159") (name "/SOCKET_39") (class "Default")
      (node (ref "J8") (pin "40") (pinfunction "BD13_40") (pintype "passive"))
      (node (ref "J9") (pin "39") (pinfunction "39_39") (pintype "passive"))
    )
    (net (code "160") (name "/SOCKET_40") (class "Default")
      (node (ref "J8") (pin "39") (pinfunction "BD12_39") (pintype "passive"))
      (node (ref "J9") (pin "40") (pinfunction "40_40") (pintype "passive"))
    )
    (net (code "161") (name "/SOCKET_41") (class "Default")
      (node (ref "J8") (pin "42") (pinfunction "BD15_42") (pintype "passive"))
      (node (ref "J9") (pin "41") (pinfunction "41_41") (pintype "passive"))
    )
    (net (code "162") (name "/SOCKET_42") (class "Default")
      (node (ref "J8") (pin "41") (pinfunction "BD14_41") (pintype "passive"))
      (node (ref "J9") (pin "42") (pinfunction "42_42") (pintype "passive"))
    )
    (net (code "163") (name "/SOCKET_43") (class "Default")
      (node (ref "J8") (pin "44") (pinfunction "DGND_44") (pintype "passive"))
      (node (ref "J9") (pin "43") (pinfunction "43_43") (pintype "passive"))
    )
    (net (code "164") (name "/SOCKET_44") (class "Default")
      (node (ref "J8") (pin "43") (pinfunction "DGND_43") (pintype "passive"))
      (node (ref "J9") (pin "44") (pinfunction "44_44") (pintype "passive"))
    )
    (net (code "165") (name "/SOCKET_45") (class "Default")
      (node (ref "J8") (pin "46") (pinfunction "+5V_46") (pintype "passive"))
      (node (ref "J9") (pin "45") (pinfunction "45_45") (pintype "passive"))
    )
    (net (code "166") (name "/SOCKET_46") (class "Default")
      (node (ref "J8") (pin "45") (pinfunction "+5V_45") (pintype "passive"))
      (node (ref "J9") (pin "46") (pinfunction "46_46") (pintype "passive"))
    )
    (net (code "167") (name "/SOCKET_47") (class "Default")
      (node (ref "J8") (pin "48") (pinfunction "A2_48") (pintype "passive"))
      (node (ref "J9") (pin "47") (pinfunction "47_47") (pintype "passive"))
    )
    (net (code "168") (name "/SOCKET_48") (class "Default")
      (node (ref "J8") (pin "47") (pinfunction "A1_47") (pintype "passive"))
      (node (ref "J9") (pin "48") (pinfunction "48_48") (pintype "passive"))
    )
    (net (code "169") (name "/SOCKET_49") (class "Default")
      (node (ref "J8") (pin "50") (pinfunction "A4_50") (pintype "passive"))
      (node (ref "J9") (pin "49") (pinfunction "49_49") (pintype "passive"))
    )
    (net (code "170") (name "/SOCKET_50") (class "Default")
      (node (ref "J8") (pin "49") (pinfunction "A3_49") (pintype "passive"))
      (node (ref "J9") (pin "50") (pinfunction "50_50") (pintype "passive"))
    )
    (net (code "171") (name "/SOCKET_51") (class "Default")
      (node (ref "J8") (pin "52") (pinfunction "A6_52") (pintype "passive"))
      (node (ref "J9") (pin "51") (pinfunction "51_51") (pintype "passive"))
    )
    (net (code "172") (name "/SOCKET_52") (class "Default")
      (node (ref "J8") (pin "51") (pinfunction "A5_51") (pintype "passive"))
      (node (ref "J9") (pin "52") (pinfunction "52_52") (pintype "passive"))
    )
    (net (code "173") (name "/SOCKET_53") (class "Default")
      (node (ref "J8") (pin "54") (pinfunction "A8_54") (pintype "passive"))
      (node (ref "J9") (pin "53") (pinfunction "53_53") (pintype "passive"))
    )
    (net (code "174") (name "/SOCKET_54") (class "Default")
      (node (ref "J8") (pin "53") (pinfunction "A7_53") (pintype "passive"))
      (node (ref "J9") (pin "54") (pinfunction "54_54") (pintype "passive"))
    )
    (net (code "175") (name "/SOCKET_55") (class "Default")
      (node (ref "J8") (pin "56") (pinfunction "A10_56") (pintype "passive"))
      (node (ref "J9") (pin "55") (pinfunction "55_55") (pintype "passive"))
    )
    (net (code "176") (name "/SOCKET_56") (class "Default")
      (node (ref "J8") (pin "55") (pinfunction "A9_55") (pintype "passive"))
      (node (ref "J9") (pin "56") (pinfunction "56_56") (pintype "passive"))
    )
    (net (code "177") (name "/SOCKET_57") (class "Default")
      (node (ref "J8") (pin "58") (pinfunction "A12_58") (pintype "passive"))
      (node (ref "J9") (pin "57") (pinfunction "57_57") (pintype "passive"))
    )
    (net (code "178") (name "/SOCKET_58") (class "Default")
      (node (ref "J8") (pin "57") (pinfunction "A11_57") (pintype "passive"))
      (node (ref "J9") (pin "58") (pinfunction "58_58") (pintype "passive"))
    )
    (net (code "179") (name "/SOCKET_59") (class "Default")
      (node (ref "J8") (pin "60") (pinfunction "/VPA_60") (pintype "passive"))
      (node (ref "J9") (pin "59") (pinfunction "59_59") (pintype "passive"))
    )
    (net (code "180") (name "/SOCKET_60") (class "Default")
      (node (ref "J8") (pin "59") (pinfunction "/VMA_59") (pintype "passive"))
      (node (ref "J9") (pin "60") (pinfunction "60_60") (pintype "passive"))
    )
    (net (code "181") (name "/SOCKET_61") (class "Default")
      (node (ref "J8") (pin "62") (pinfunction "/DTACK_62") (pintype "passive"))
      (node (ref "J9") (pin "61") (pinfunction "61_61") (pintype "passive"))
    )
    (net (code "182") (name "/SOCKET_62") (class "Default")
      (node (ref "J8") (pin "61") (pinfunction "+12V_61") (pintype "passive"))
      (node (ref "J9") (pin "62") (pinfunction "62_62") (pintype "passive"))
    )
    (net (code "183") (name "/SOCKET_63") (class "Default")
      (node (ref "J8") (pin "64") (pinfunction "READ_64") (pintype "passive"))
      (node (ref "J9") (pin "63") (pinfunction "63_63") (pintype "passive"))
    )
    (net (code "184") (name "/SOCKET_64") (class "Default")
      (node (ref "J8") (pin "63") (pinfunction "/AS_63") (pintype "passive"))
      (node (ref "J9") (pin "64") (pinfunction "64_64") (pintype "passive"))
    )
    (net (code "185") (name "/SOCKET_65") (class "Default")
      (node (ref "J8") (pin "66") (pinfunction "/UDS_66") (pintype "passive"))
      (node (ref "J9") (pin "65") (pinfunction "65_65") (pintype "passive"))
    )
    (net (code "186") (name "/SOCKET_66") (class "Default")
      (node (ref "J8") (pin "65") (pinfunction "/LDS_65") (pintype "passive"))
      (node (ref "J9") (pin "66") (pinfunction "66_66") (pintype "passive"))
    )
    (net (code "187") (name "/SOCKET_67") (class "Default")
      (node (ref "J8") (pin "68") (pinfunction "/INTIO_68") (pintype "passive"))
      (node (ref "J9") (pin "67") (pinfunction "67_67") (pintype "passive"))
    )
    (net (code "188") (name "/SOCKET_68") (class "Default")
      (node (ref "J8") (pin "67") (pinfunction "/CSYNC_67") (pintype "passive"))
      (node (ref "J9") (pin "68") (pinfunction "68_68") (pintype "passive"))
    )
    (net (code "189") (name "/SOCKET_69") (class "Default")
      (node (ref "J8") (pin "70") (pinfunction "VA9B_70") (pintype "passive"))
      (node (ref "J9") (pin "69") (pinfunction "69_69") (pintype "passive"))
    )
    (net (code "190") (name "/SOCKET_70") (class "Default")
      (node (ref "J8") (pin "69") (pinfunction "VA10B_69") (pintype "passive"))
      (node (ref "J9") (pin "70") (pinfunction "70_70") (pintype "passive"))
    )
    (net (code "191") (name "/SOCKET_71") (class "Default")
      (node (ref "J8") (pin "72") (pinfunction "R2_72") (pintype "passive"))
      (node (ref "J9") (pin "71") (pinfunction "71_71") (pintype "passive"))
    )
    (net (code "192") (name "/SOCKET_72") (class "Default")
      (node (ref "J8") (pin "71") (pinfunction "R1_71") (pintype "passive"))
      (node (ref "J9") (pin "72") (pinfunction "72_72") (pintype "passive"))
    )
    (net (code "193") (name "/SOCKET_73") (class "Default")
      (node (ref "J8") (pin "74") (pinfunction "MD1_74") (pintype "passive"))
      (node (ref "J9") (pin "73") (pinfunction "73_73") (pintype "passive"))
    )
    (net (code "194") (name "/SOCKET_74") (class "Default")
      (node (ref "J8") (pin "73") (pinfunction "MD0_73") (pintype "passive"))
      (node (ref "J9") (pin "74") (pinfunction "74_74") (pintype "passive"))
    )
    (net (code "195") (name "/SOCKET_75") (class "Default")
      (node (ref "J8") (pin "76") (pinfunction "MD3_76") (pintype "passive"))
      (node (ref "J9") (pin "75") (pinfunction "75_75") (pintype "passive"))
    )
    (net (code "196") (name "/SOCKET_76") (class "Default")
      (node (ref "J8") (pin "75") (pinfunction "MD2_75") (pintype "passive"))
      (node (ref "J9") (pin "76") (pinfunction "76_76") (pintype "passive"))
    )
    (net (code "197") (name "/SOCKET_77") (class "Default")
      (node (ref "J8") (pin "78") (pinfunction "MD5_78") (pintype "passive"))
      (node (ref "J9") (pin "77") (pinfunction "77_77") (pintype "passive"))
    )
    (net (code "198") (name "/SOCKET_78") (class "Default")
      (node (ref "J8") (pin "77") (pinfunction "MD4_77") (pintype "passive"))
      (node (ref "J9") (pin "78") (pinfunction "78_78") (pintype "passive"))
    )
    (net (code "199") (name "/SOCKET_79") (class "Default")
      (node (ref "J8") (pin "80") (pinfunction "MD7_80") (pintype "passive"))
      (node (ref "J9") (pin "79") (pinfunction "79_79") (pintype "passive"))
    )
    (net (code "200") (name "/SOCKET_80") (class "Default")
      (node (ref "J8") (pin "79") (pinfunction "MD6_79") (pintype "passive"))
      (node (ref "J9") (pin "80") (pinfunction "80_80") (pintype "passive"))
    )
    (net (code "201") (name "/SOCKET_81") (class "Default")
      (node (ref "J8") (pin "82") (pinfunction "MD9_82") (pintype "passive"))
      (node (ref "J9") (pin "81") (pinfunction "81_81") (pintype "passive"))
    )
    (net (code "202") (name "/SOCKET_82") (class "Default")
      (node (ref "J8") (pin "81") (pinfunction "MD8_81") (pintype "passive"))
      (node (ref "J9") (pin "82") (pinfunction "82_82") (pintype "passive"))
    )
    (net (code "203") (name "/SOCKET_83") (class "Default")
      (node (ref "J8") (pin "84") (pinfunction "MD11_84") (pintype "passive"))
      (node (ref "J9") (pin "83") (pinfunction "83_83") (pintype "passive"))
    )
    (net (code "204") (name "/SOCKET_84") (class "Default")
      (node (ref "J8") (pin "83") (pinfunction "MD10_83") (pintype "passive"))
      (node (ref "J9") (pin "84") (pinfunction "84_84") (pintype "passive"))
    )
    (net (code "205") (name "/SOCKET_85") (class "Default")
      (node (ref "J8") (pin "86") (pinfunction "MD13_86") (pintype "passive"))
      (node (ref "J9") (pin "85") (pinfunction "85_85") (pintype "passive"))
    )
    (net (code "206") (name "/SOCKET_86") (class "Default")
      (node (ref "J8") (pin "85") (pinfunction "MD12_85") (pintype "passive"))
      (node (ref "J9") (pin "86") (pinfunction "86_86") (pintype "passive"))
    )
    (net (code "207") (name "/SOCKET_87") (class "Default")
      (node (ref "J8") (pin "88") (pinfunction "MD15_88") (pintype "passive"))
      (node (ref "J9") (pin "87") (pinfunction "87_87") (pintype "passive"))
    )
    (net (code "208") (name "/SOCKET_88") (class "Default")
      (node (ref "J8") (pin "87") (pinfunction "MD14_87") (pintype "passive"))
      (node (ref "J9") (pin "88") (pinfunction "88_88") (pintype "passive"))
    )
    (net (code "209") (name "/SOCKET_89") (class "Default")
      (node (ref "J8") (pin "90") (pinfunction "DGND_90") (pintype "passive"))
      (node (ref "J9") (pin "89") (pinfunction "89_89") (pintype "passive"))
    )
    (net (code "210") (name "/SOCKET_90") (class "Default")
      (node (ref "J8") (pin "89") (pinfunction "DGND_89") (pintype "passive"))
      (node (ref "J9") (pin "90") (pinfunction "90_90") (pintype "passive"))
    )
    (net (code "211") (name "/SOCKET_91") (class "Default")
      (node (ref "J8") (pin "92") (pinfunction "+5V_92") (pintype "passive"))
      (node (ref "J9") (pin "91") (pinfunction "91_91") (pintype "passive"))
    )
    (net (code "212") (name "/SOCKET_92") (class "Default")
      (node (ref "J8") (pin "91") (pinfunction "+5V_91") (pintype "passive"))
      (node (ref "J9") (pin "92") (pinfunction "92_92") (pintype "passive"))
    )
    (net (code "213") (name "/SOCKET_93") (class "Default")
      (node (ref "J8") (pin "94") (pinfunction "RA2_94") (pintype "passive"))
      (node (ref "J9") (pin "93") (pinfunction "93_93") (pintype "passive"))
    )
    (net (code "214") (name "/SOCKET_94") (class "Default")
      (node (ref "J8") (pin "93") (pinfunction "RA1_93") (pintype "passive"))
      (node (ref "J9") (pin "94") (pinfunction "94_94") (pintype "passive"))
    )
    (net (code "215") (name "/SOCKET_95") (class "Default")
      (node (ref "J8") (pin "96") (pinfunction "RA4_96") (pintype "passive"))
      (node (ref "J9") (pin "95") (pinfunction "95_95") (pintype "passive"))
    )
    (net (code "216") (name "/SOCKET_96") (class "Default")
      (node (ref "J8") (pin "95") (pinfunction "RA3_95") (pintype "passive"))
      (node (ref "J9") (pin "96") (pinfunction "96_96") (pintype "passive"))
    )
    (net (code "217") (name "/SOCKET_97") (class "Default")
      (node (ref "J8") (pin "98") (pinfunction "RA6_98") (pintype "passive"))
      (node (ref "J9") (pin "97") (pinfunction "97_97") (pintype "passive"))
    )
    (net (code "218") (name "/SOCKET_98") (class "Default")
      (node (ref "J8") (pin "97") (pinfunction "RA5_97") (pintype "passive"))
      (node (ref "J9") (pin "98") (pinfunction "98_98") (pintype "passive"))
    )
    (net (code "219") (name "/SOCKET_99") (class "Default")
      (node (ref "J8") (pin "100") (pinfunction "RA8_100") (pintype "passive"))
      (node (ref "J9") (pin "99") (pinfunction "99_99") (pintype "passive"))
    )
    (net (code "220") (name "/SOCKET_100") (class "Default")
      (node (ref "J8") (pin "99") (pinfunction "RA7_99") (pintype "passive"))
      (node (ref "J9") (pin "100") (pinfunction "100_100") (pintype "passive"))
    )
    (net (code "221") (name "/SOCKET_101") (class "Default")
      (node (ref "J8") (pin "102") (pinfunction "A16_102") (pintype "passive"))
      (node (ref "J9") (pin "101") (pinfunction "101_101") (pintype "passive"))
    )
    (net (code "222") (name "/SOCKET_102") (class "Default")
      (node (ref "J8") (pin "101") (pinfunction "/RSTSW_101") (pintype "passive"))
      (node (ref "J9") (pin "102") (pinfunction "102_102") (pintype "passive"))
    )
    (net (code "223") (name "/SOCKET_103") (class "Default")
      (node (ref "J8") (pin "104") (pinfunction "A18_104") (pintype "passive"))
      (node (ref "J9") (pin "103") (pinfunction "103_103") (pintype "passive"))
    )
    (net (code "224") (name "/SOCKET_104") (class "Default")
      (node (ref "J8") (pin "103") (pinfunction "A17_103") (pintype "passive"))
      (node (ref "J9") (pin "104") (pinfunction "104_104") (pintype "passive"))
    )
    (net (code "225") (name "/SOCKET_105") (class "Default")
      (node (ref "J8") (pin "106") (pinfunction "DOTCK_106") (pintype "passive"))
      (node (ref "J9") (pin "105") (pinfunction "105_105") (pintype "passive"))
    )
    (net (code "226") (name "/SOCKET_106") (class "Default")
      (node (ref "J8") (pin "105") (pinfunction "A19_105") (pintype "passive"))
      (node (ref "J9") (pin "106") (pinfunction "106_106") (pintype "passive"))
    )
    (net (code "227") (name "/SOCKET_107") (class "Default")
      (node (ref "J8") (pin "108") (pinfunction "/CAS_108") (pintype "passive"))
      (node (ref "J9") (pin "107") (pinfunction "107_107") (pintype "passive"))
    )
    (net (code "228") (name "/SOCKET_108") (class "Default")
      (node (ref "J8") (pin "107") (pinfunction "MREAD_107") (pintype "passive"))
      (node (ref "J9") (pin "108") (pinfunction "108_108") (pintype "passive"))
    )
    (net (code "229") (name "/SOCKET_109") (class "Default")
      (node (ref "J8") (pin "110") (pinfunction "A20_110") (pintype "passive"))
      (node (ref "J9") (pin "109") (pinfunction "109_109") (pintype "passive"))
    )
    (net (code "230") (name "/SOCKET_110") (class "Default")
      (node (ref "J8") (pin "109") (pinfunction "/RAS_109") (pintype "passive"))
      (node (ref "J9") (pin "110") (pinfunction "110_110") (pintype "passive"))
    )
    (net (code "231") (name "/SOCKET_111") (class "Default")
      (node (ref "J8") (pin "112") (pinfunction "/HDER_112") (pintype "passive"))
      (node (ref "J9") (pin "111") (pinfunction "111_111") (pintype "passive"))
    )
    (net (code "232") (name "/SOCKET_112") (class "Default")
      (node (ref "J8") (pin "111") (pinfunction "/HSYNC_111") (pintype "passive"))
      (node (ref "J9") (pin "112") (pinfunction "112_112") (pintype "passive"))
    )
    (net (code "233") (name "/SOCKET_113") (class "Default")
      (node (ref "J8") (pin "114") (pinfunction "/SFER_114") (pintype "passive"))
      (node (ref "J9") (pin "113") (pinfunction "113_113") (pintype "passive"))
    )
    (net (code "234") (name "/SOCKET_114") (class "Default")
      (node (ref "J8") (pin "113") (pinfunction "/VSYNC_113") (pintype "passive"))
      (node (ref "J9") (pin "114") (pinfunction "114_114") (pintype "passive"))
    )
    (net (code "235") (name "/SOCKET_115") (class "Default")
      (node (ref "J8") (pin "116") (pinfunction "/NMI_116") (pintype "passive"))
      (node (ref "J9") (pin "115") (pinfunction "115_115") (pintype "passive"))
    )
    (net (code "236") (name "/SOCKET_116") (class "Default")
      (node (ref "J8") (pin "115") (pinfunction "VID_115") (pintype "passive"))
      (node (ref "J9") (pin "116") (pinfunction "116_116") (pintype "passive"))
    )
    (net (code "237") (name "/SOCKET_117") (class "Default")
      (node (ref "J8") (pin "118") (pinfunction "DGND_118") (pintype "passive"))
      (node (ref "J9") (pin "117") (pinfunction "117_117") (pintype "passive"))
    )
    (net (code "238") (name "/SOCKET_118") (class "Default")
      (node (ref "J8") (pin "117") (pinfunction "DGND_117") (pintype "passive"))
      (node (ref "J9") (pin "118") (pinfunction "118_118") (pintype "passive"))
    )
    (net (code "239") (name "/SOCKET_119") (class "Default")
      (node (ref "J8") (pin "120") (pinfunction "+5V_120") (pintype "passive"))
      (node (ref "J9") (pin "119") (pinfunction "119_119") (pintype "passive"))
    )
    (net (code "240") (name "/SOCKET_120") (class "Default")
      (node (ref "J8") (pin "119") (pinfunction "+5V_119") (pintype "passive"))
      (node (ref "J9") (pin "120") (pinfunction "120_120") (pintype "passive"))
    )
  )
)
